# electrophy_MCU.net
KiCad netlist of a schematic drawn in EAGLE
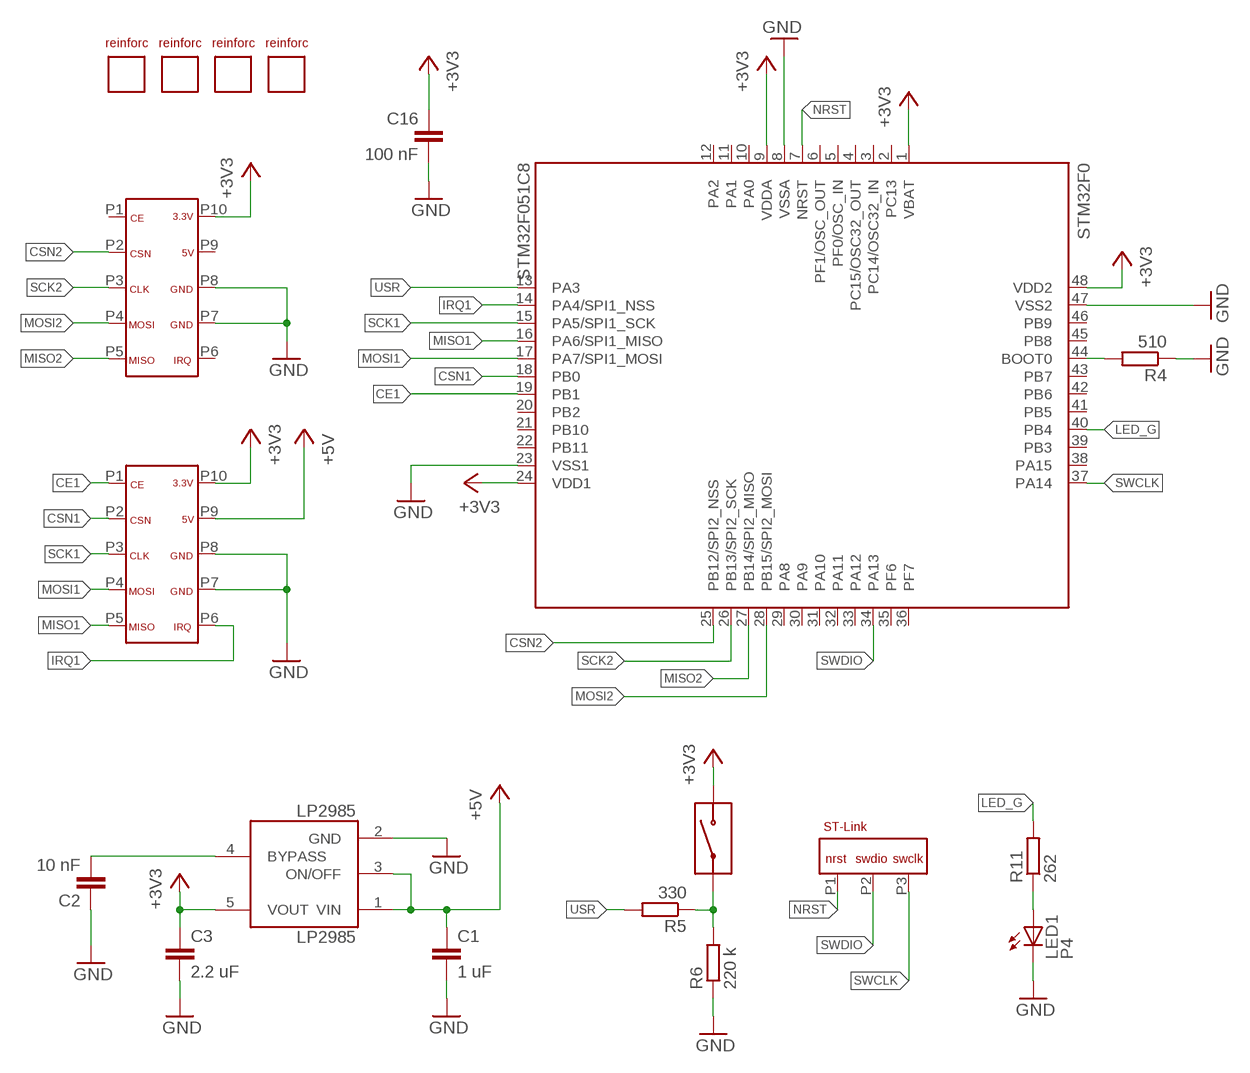
[diagram p0: schematic, sheet 1]

(export (version "E")
  (design (tool "Eeschema 10.0.6"))
  (components
    (comp (ref "C1")
      (value "1 uF")
      (footprint "eagle-import:C0603")
      (libsource (lib "eagle-import") (part "C-EUC0603"))
    )
    (comp (ref "C2")
      (value "10 nF")
      (footprint "eagle-import:C0603")
      (libsource (lib "eagle-import") (part "C-EUC0603"))
    )
    (comp (ref "C3")
      (value "2.2 uF")
      (footprint "eagle-import:C0603")
      (libsource (lib "eagle-import") (part "C-EUC0603"))
    )
    (comp (ref "C16")
      (value "100 nF")
      (footprint "eagle-import:C0603")
      (libsource (lib "eagle-import") (part "C-EUC0603"))
    )
    (comp (ref "LED1")
      (value "P4")
      (footprint "eagle-import:CHIPLED_0603")
      (libsource (lib "eagle-import") (part "P4"))
    )
    (comp (ref "LP2985")
      (value "LP2985AIM5-3.3")
      (footprint "eagle-import:SOT25")
      (libsource (lib "eagle-import") (part "LP2985AIM5-3.3"))
    )
    (comp (ref "R4")
      (value "510")
      (footprint "eagle-import:R0603")
      (libsource (lib "eagle-import") (part "R-EU_R0603"))
    )
    (comp (ref "R5")
      (value "330")
      (footprint "eagle-import:R0603")
      (libsource (lib "eagle-import") (part "R-EU_R0603"))
    )
    (comp (ref "R6")
      (value "220 k")
      (footprint "eagle-import:R0603")
      (libsource (lib "eagle-import") (part "R-EU_R0603"))
    )
    (comp (ref "R11")
      (value "262")
      (footprint "eagle-import:R0603")
      (libsource (lib "eagle-import") (part "R-EU_R0603"))
    )
    (comp (ref "STM32F0")
      (value "STM32F051C8")
      (footprint "eagle-import:LQFP48-7X7")
      (libsource (lib "eagle-import") (part "STM32F051C8"))
    )
    (comp (ref "U$1")
      (value "DF12-10-FEMALE")
      (footprint "eagle-import:DF12-10-FEMALE")
      (libsource (lib "eagle-import") (part "DF12-10-FEMALE"))
    )
    (comp (ref "U$2")
      (value "PROGRAM_PIN")
      (footprint "eagle-import:PROGRAM_PIN")
      (libsource (lib "eagle-import") (part "PROGRAM_PIN"))
    )
    (comp (ref "U$3")
      (value "DF12-10-MALE")
      (footprint "eagle-import:DF12-10-MALE")
      (libsource (lib "eagle-import") (part "DF12-10-MALE"))
    )
    (comp (ref "U$4")
      (value "TACTILE_BUTTON_THROUGH")
      (footprint "eagle-import:TACTILE_BUTTON_THROUGH")
      (libsource (lib "eagle-import") (part "TACTILE_BUTTON_THROUGH"))
    )
    (comp (ref "U$5")
      (value "REINFORCEMENT")
      (footprint "eagle-import:REINFORCEMENT")
      (libsource (lib "eagle-import") (part "REINFORCEMENT"))
    )
    (comp (ref "U$6")
      (value "REINFORCEMENT")
      (footprint "eagle-import:REINFORCEMENT")
      (libsource (lib "eagle-import") (part "REINFORCEMENT"))
    )
    (comp (ref "U$7")
      (value "REINFORCEMENT")
      (footprint "eagle-import:REINFORCEMENT")
      (libsource (lib "eagle-import") (part "REINFORCEMENT"))
    )
    (comp (ref "U$8")
      (value "REINFORCEMENT")
      (footprint "eagle-import:REINFORCEMENT")
      (libsource (lib "eagle-import") (part "REINFORCEMENT"))
    )
  )
  (nets
    (net (code "1") (name "+3V3") (class "Default")
      (node (ref "C16") (pin "1") (pinfunction "1_1") (pintype "passive"))
      (node (ref "C3") (pin "1") (pinfunction "1_1") (pintype "passive"))
      (node (ref "LP2985") (pin "5") (pinfunction "VOUT_5") (pintype "power_in"))
      (node (ref "STM32F0") (pin "1") (pinfunction "VBAT_1") (pintype "bidirectional"))
      (node (ref "STM32F0") (pin "24") (pinfunction "VDD1_24") (pintype "bidirectional"))
      (node (ref "STM32F0") (pin "48") (pinfunction "VDD2_48") (pintype "bidirectional"))
      (node (ref "STM32F0") (pin "9") (pinfunction "VDDA_9") (pintype "bidirectional"))
      (node (ref "U$1") (pin "P10") (pinfunction "P10_P10") (pintype "passive"))
      (node (ref "U$3") (pin "P10") (pinfunction "P10_P10") (pintype "passive"))
      (node (ref "U$4") (pin "P2") (pinfunction "2_P2") (pintype "bidirectional"))
    )
    (net (code "2") (name "+5V") (class "Default")
      (node (ref "C1") (pin "1") (pinfunction "1_1") (pintype "passive"))
      (node (ref "LP2985") (pin "1") (pinfunction "VIN_1") (pintype "power_in"))
      (node (ref "LP2985") (pin "3") (pinfunction "ON/OFF_3") (pintype "bidirectional"))
      (node (ref "U$1") (pin "P9") (pinfunction "P9_P9") (pintype "passive"))
    )
    (net (code "3") (name "CE1") (class "Default")
      (node (ref "STM32F0") (pin "19") (pinfunction "PB1_19") (pintype "bidirectional"))
      (node (ref "U$1") (pin "P1") (pinfunction "P1_P1") (pintype "passive"))
    )
    (net (code "4") (name "CSN1") (class "Default")
      (node (ref "STM32F0") (pin "18") (pinfunction "PB0_18") (pintype "bidirectional"))
      (node (ref "U$1") (pin "P2") (pinfunction "P2_P2") (pintype "passive"))
    )
    (net (code "5") (name "CSN2") (class "Default")
      (node (ref "STM32F0") (pin "25") (pinfunction "PB12/SPI2_NSS_25") (pintype "bidirectional"))
      (node (ref "U$3") (pin "P2") (pinfunction "P2_P2") (pintype "passive"))
    )
    (net (code "6") (name "GND") (class "Default")
      (node (ref "C1") (pin "2") (pinfunction "2_2") (pintype "passive"))
      (node (ref "C16") (pin "2") (pinfunction "2_2") (pintype "passive"))
      (node (ref "C2") (pin "1") (pinfunction "1_1") (pintype "passive"))
      (node (ref "C3") (pin "2") (pinfunction "2_2") (pintype "passive"))
      (node (ref "LED1") (pin "C") (pinfunction "C_C") (pintype "passive"))
      (node (ref "LP2985") (pin "2") (pinfunction "GND_2") (pintype "power_in"))
      (node (ref "R4") (pin "1") (pinfunction "1_1") (pintype "passive"))
      (node (ref "R6") (pin "1") (pinfunction "1_1") (pintype "passive"))
      (node (ref "STM32F0") (pin "23") (pinfunction "VSS1_23") (pintype "bidirectional"))
      (node (ref "STM32F0") (pin "47") (pinfunction "VSS2_47") (pintype "bidirectional"))
      (node (ref "STM32F0") (pin "8") (pinfunction "VSSA_8") (pintype "bidirectional"))
      (node (ref "U$1") (pin "P7") (pinfunction "P7_P7") (pintype "passive"))
      (node (ref "U$1") (pin "P8") (pinfunction "P8_P8") (pintype "passive"))
      (node (ref "U$3") (pin "P7") (pinfunction "P7_P7") (pintype "passive"))
      (node (ref "U$3") (pin "P8") (pinfunction "P8_P8") (pintype "passive"))
    )
    (net (code "7") (name "IRQ1") (class "Default")
      (node (ref "STM32F0") (pin "14") (pinfunction "PA4/SPI1_NSS_14") (pintype "bidirectional"))
      (node (ref "U$1") (pin "P6") (pinfunction "P6_P6") (pintype "passive"))
    )
    (net (code "8") (name "LED_G") (class "Default")
      (node (ref "R11") (pin "2") (pinfunction "2_2") (pintype "passive"))
      (node (ref "STM32F0") (pin "40") (pinfunction "PB4_40") (pintype "bidirectional"))
    )
    (net (code "9") (name "MISO1") (class "Default")
      (node (ref "STM32F0") (pin "16") (pinfunction "PA6/SPI1_MISO_16") (pintype "bidirectional"))
      (node (ref "U$1") (pin "P5") (pinfunction "P5_P5") (pintype "passive"))
    )
    (net (code "10") (name "MISO2") (class "Default")
      (node (ref "STM32F0") (pin "27") (pinfunction "PB14/SPI2_MISO_27") (pintype "bidirectional"))
      (node (ref "U$3") (pin "P5") (pinfunction "P5_P5") (pintype "passive"))
    )
    (net (code "11") (name "MOSI1") (class "Default")
      (node (ref "STM32F0") (pin "17") (pinfunction "PA7/SPI1_MOSI_17") (pintype "bidirectional"))
      (node (ref "U$1") (pin "P4") (pinfunction "P4_P4") (pintype "passive"))
    )
    (net (code "12") (name "MOSI2") (class "Default")
      (node (ref "STM32F0") (pin "28") (pinfunction "PB15/SPI2_MOSI_28") (pintype "bidirectional"))
      (node (ref "U$3") (pin "P4") (pinfunction "P4_P4") (pintype "passive"))
    )
    (net (code "13") (name "NRST") (class "Default")
      (node (ref "STM32F0") (pin "7") (pinfunction "NRST_7") (pintype "bidirectional"))
      (node (ref "U$2") (pin "P1") (pinfunction "P1_P1") (pintype "passive"))
    )
    (net (code "14") (name "Net-(LED1-PadA)") (class "Default")
      (node (ref "LED1") (pin "A") (pinfunction "A_A") (pintype "passive"))
      (node (ref "R11") (pin "1") (pinfunction "1_1") (pintype "passive"))
    )
    (net (code "15") (name "Net-(LP2985-BYPASS)") (class "Default")
      (node (ref "C2") (pin "2") (pinfunction "2_2") (pintype "passive"))
      (node (ref "LP2985") (pin "4") (pinfunction "BYPASS_4") (pintype "bidirectional"))
    )
    (net (code "16") (name "Net-(STM32F0-BOOT0)") (class "Default")
      (node (ref "R4") (pin "2") (pinfunction "2_2") (pintype "passive"))
      (node (ref "STM32F0") (pin "44") (pinfunction "BOOT0_44") (pintype "bidirectional"))
    )
    (net (code "17") (name "Net-(U$4-1)") (class "Default")
      (node (ref "R5") (pin "1") (pinfunction "1_1") (pintype "passive"))
      (node (ref "R6") (pin "2") (pinfunction "2_2") (pintype "passive"))
      (node (ref "U$4") (pin "P1") (pinfunction "1_P1") (pintype "bidirectional"))
    )
    (net (code "18") (name "SCK1") (class "Default")
      (node (ref "STM32F0") (pin "15") (pinfunction "PA5/SPI1_SCK_15") (pintype "bidirectional"))
      (node (ref "U$1") (pin "P3") (pinfunction "P3_P3") (pintype "passive"))
    )
    (net (code "19") (name "SCK2") (class "Default")
      (node (ref "STM32F0") (pin "26") (pinfunction "PB13/SPI2_SCK_26") (pintype "bidirectional"))
      (node (ref "U$3") (pin "P3") (pinfunction "P3_P3") (pintype "passive"))
    )
    (net (code "20") (name "SWCLK") (class "Default")
      (node (ref "STM32F0") (pin "37") (pinfunction "PA14_37") (pintype "bidirectional"))
      (node (ref "U$2") (pin "P3") (pinfunction "P3_P3") (pintype "passive"))
    )
    (net (code "21") (name "SWDIO") (class "Default")
      (node (ref "STM32F0") (pin "34") (pinfunction "PA13_34") (pintype "bidirectional"))
      (node (ref "U$2") (pin "P2") (pinfunction "P2_P2") (pintype "passive"))
    )
    (net (code "22") (name "USR") (class "Default")
      (node (ref "R5") (pin "2") (pinfunction "2_2") (pintype "passive"))
      (node (ref "STM32F0") (pin "13") (pinfunction "PA3_13") (pintype "bidirectional"))
    )
    (net (code "23") (name "unconnected-(STM32F0-PA0-Pad10)") (class "Default")
      (node (ref "STM32F0") (pin "10") (pinfunction "PA0_10") (pintype "bidirectional"))
    )
    (net (code "24") (name "unconnected-(STM32F0-PA1-Pad11)") (class "Default")
      (node (ref "STM32F0") (pin "11") (pinfunction "PA1_11") (pintype "bidirectional"))
    )
    (net (code "25") (name "unconnected-(STM32F0-PA2-Pad12)") (class "Default")
      (node (ref "STM32F0") (pin "12") (pinfunction "PA2_12") (pintype "bidirectional"))
    )
    (net (code "26") (name "unconnected-(STM32F0-PA8-Pad29)") (class "Default")
      (node (ref "STM32F0") (pin "29") (pinfunction "PA8_29") (pintype "bidirectional"))
    )
    (net (code "27") (name "unconnected-(STM32F0-PA9-Pad30)") (class "Default")
      (node (ref "STM32F0") (pin "30") (pinfunction "PA9_30") (pintype "bidirectional"))
    )
    (net (code "28") (name "unconnected-(STM32F0-PA10-Pad31)") (class "Default")
      (node (ref "STM32F0") (pin "31") (pinfunction "PA10_31") (pintype "bidirectional"))
    )
    (net (code "29") (name "unconnected-(STM32F0-PA11-Pad32)") (class "Default")
      (node (ref "STM32F0") (pin "32") (pinfunction "PA11_32") (pintype "bidirectional"))
    )
    (net (code "30") (name "unconnected-(STM32F0-PA12-Pad33)") (class "Default")
      (node (ref "STM32F0") (pin "33") (pinfunction "PA12_33") (pintype "bidirectional"))
    )
    (net (code "31") (name "unconnected-(STM32F0-PA15-Pad38)") (class "Default")
      (node (ref "STM32F0") (pin "38") (pinfunction "PA15_38") (pintype "bidirectional"))
    )
    (net (code "32") (name "unconnected-(STM32F0-PB2-Pad20)") (class "Default")
      (node (ref "STM32F0") (pin "20") (pinfunction "PB2_20") (pintype "bidirectional"))
    )
    (net (code "33") (name "unconnected-(STM32F0-PB3-Pad39)") (class "Default")
      (node (ref "STM32F0") (pin "39") (pinfunction "PB3_39") (pintype "bidirectional"))
    )
    (net (code "34") (name "unconnected-(STM32F0-PB5-Pad41)") (class "Default")
      (node (ref "STM32F0") (pin "41") (pinfunction "PB5_41") (pintype "bidirectional"))
    )
    (net (code "35") (name "unconnected-(STM32F0-PB6-Pad42)") (class "Default")
      (node (ref "STM32F0") (pin "42") (pinfunction "PB6_42") (pintype "bidirectional"))
    )
    (net (code "36") (name "unconnected-(STM32F0-PB7-Pad43)") (class "Default")
      (node (ref "STM32F0") (pin "43") (pinfunction "PB7_43") (pintype "bidirectional"))
    )
    (net (code "37") (name "unconnected-(STM32F0-PB8-Pad45)") (class "Default")
      (node (ref "STM32F0") (pin "45") (pinfunction "PB8_45") (pintype "bidirectional"))
    )
    (net (code "38") (name "unconnected-(STM32F0-PB9-Pad46)") (class "Default")
      (node (ref "STM32F0") (pin "46") (pinfunction "PB9_46") (pintype "bidirectional"))
    )
    (net (code "39") (name "unconnected-(STM32F0-PB10-Pad21)") (class "Default")
      (node (ref "STM32F0") (pin "21") (pinfunction "PB10_21") (pintype "bidirectional"))
    )
    (net (code "40") (name "unconnected-(STM32F0-PB11-Pad22)") (class "Default")
      (node (ref "STM32F0") (pin "22") (pinfunction "PB11_22") (pintype "bidirectional"))
    )
    (net (code "41") (name "unconnected-(STM32F0-PC13-Pad2)") (class "Default")
      (node (ref "STM32F0") (pin "2") (pinfunction "PC13_2") (pintype "bidirectional"))
    )
    (net (code "42") (name "unconnected-(STM32F0-PC14{slash}OSC32_IN-Pad3)") (class "Default")
      (node (ref "STM32F0") (pin "3") (pinfunction "PC14/OSC32_IN_3") (pintype "bidirectional"))
    )
    (net (code "43") (name "unconnected-(STM32F0-PC15{slash}OSC32_OUT-Pad4)") (class "Default")
      (node (ref "STM32F0") (pin "4") (pinfunction "PC15/OSC32_OUT_4") (pintype "bidirectional"))
    )
    (net (code "44") (name "unconnected-(STM32F0-PF0{slash}OSC_IN-Pad5)") (class "Default")
      (node (ref "STM32F0") (pin "5") (pinfunction "PF0/OSC_IN_5") (pintype "bidirectional"))
    )
    (net (code "45") (name "unconnected-(STM32F0-PF1{slash}OSC_OUT-Pad6)") (class "Default")
      (node (ref "STM32F0") (pin "6") (pinfunction "PF1/OSC_OUT_6") (pintype "bidirectional"))
    )
    (net (code "46") (name "unconnected-(STM32F0-PF6-Pad35)") (class "Default")
      (node (ref "STM32F0") (pin "35") (pinfunction "PF6_35") (pintype "bidirectional"))
    )
    (net (code "47") (name "unconnected-(STM32F0-PF7-Pad36)") (class "Default")
      (node (ref "STM32F0") (pin "36") (pinfunction "PF7_36") (pintype "bidirectional"))
    )
    (net (code "48") (name "unconnected-(U$3-PadP1)") (class "Default")
      (node (ref "U$3") (pin "P1") (pinfunction "P1_P1") (pintype "passive"))
    )
    (net (code "49") (name "unconnected-(U$3-PadP6)") (class "Default")
      (node (ref "U$3") (pin "P6") (pinfunction "P6_P6") (pintype "passive"))
    )
    (net (code "50") (name "unconnected-(U$3-PadP9)") (class "Default")
      (node (ref "U$3") (pin "P9") (pinfunction "P9_P9") (pintype "passive"))
    )
    (net (code "51") (name "unconnected-(U$5-PadP$1)") (class "Default")
      (node (ref "U$5") (pin "P$1") (pinfunction "P$1_P$1") (pintype "bidirectional"))
    )
    (net (code "52") (name "unconnected-(U$6-PadP$1)") (class "Default")
      (node (ref "U$6") (pin "P$1") (pinfunction "P$1_P$1") (pintype "bidirectional"))
    )
    (net (code "53") (name "unconnected-(U$7-PadP$1)") (class "Default")
      (node (ref "U$7") (pin "P$1") (pinfunction "P$1_P$1") (pintype "bidirectional"))
    )
    (net (code "54") (name "unconnected-(U$8-PadP$1)") (class "Default")
      (node (ref "U$8") (pin "P$1") (pinfunction "P$1_P$1") (pintype "bidirectional"))
    )
  )
)
